# PowerB.net
KiCad netlist of a schematic drawn in Altium Designer
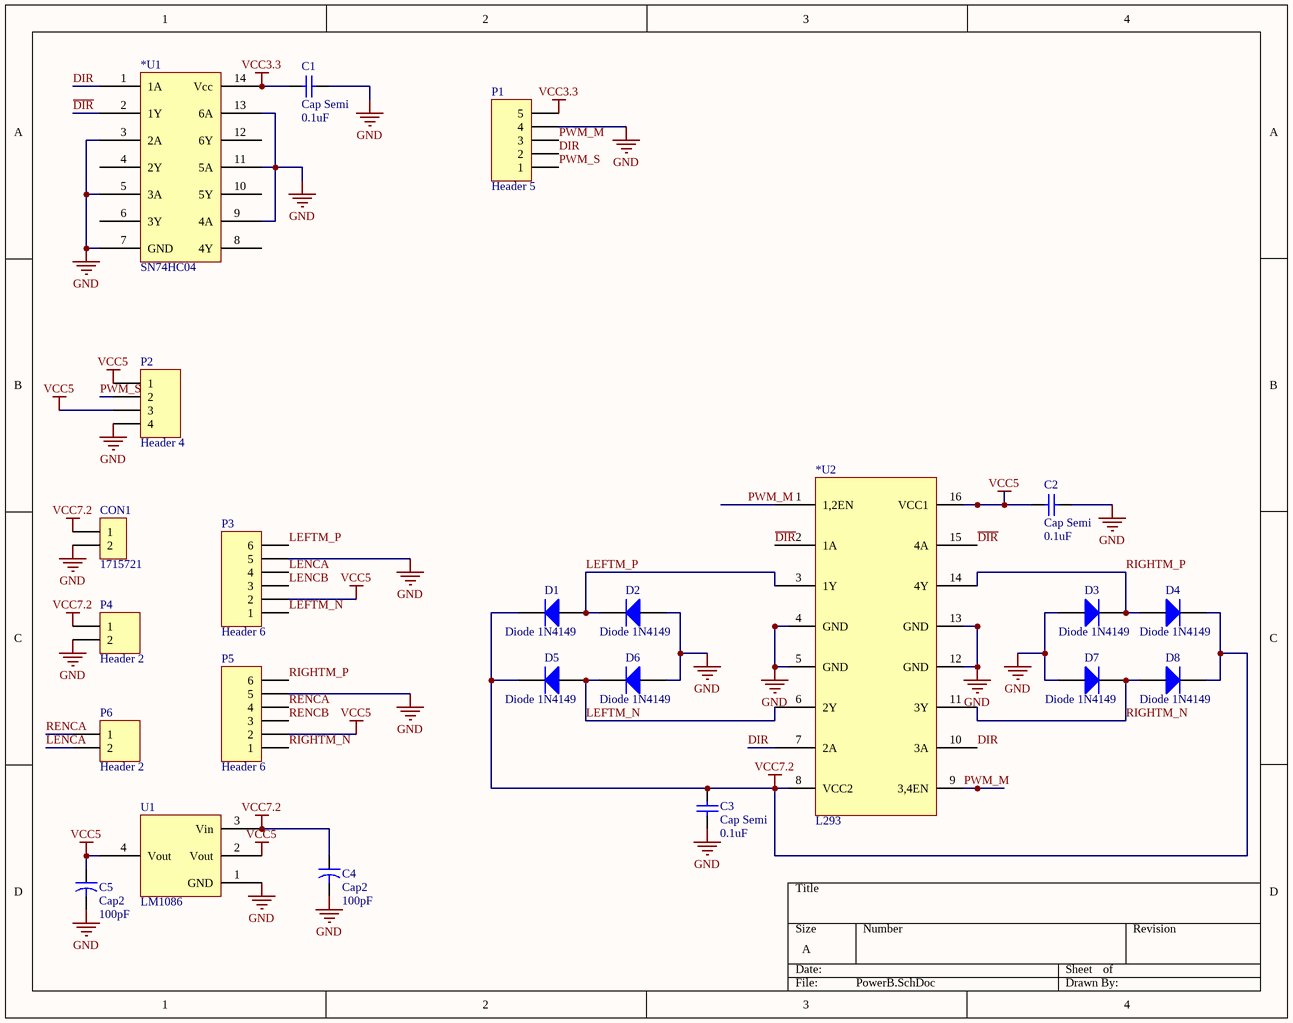
[diagram p0: PowerB.SchDoc]

(export (version "E")
  (design (tool "Eeschema 10.0.6"))
  (components
    (comp (ref "*U1")
      (value "SN74HC04")
      (footprint "Atmel Industrial Control:DIP14")
      (libsource (lib "SN74HC04") (part "SN74HC04"))
    )
    (comp (ref "*U2")
      (value "L293")
      (footprint "Dallas Communication PCM Circuit:DIP16")
      (libsource (lib "L293") (part "L293"))
    )
    (comp (ref "C1")
      (value "Cap Semi")
      (footprint "C1206")
      (description "Capacitor (Semiconductor SIM Model)")
      (fields (field (name "ALTIUM_VALUE") "0.1uF") (field (name "PUBLISHER") "Altium Limited"))
      (libsource (lib "Miscellaneous Devices") (part "Cap Semi"))
    )
    (comp (ref "C2")
      (value "Cap Semi")
      (footprint "C1206")
      (description "Capacitor (Semiconductor SIM Model)")
      (fields (field (name "ALTIUM_VALUE") "0.1uF") (field (name "PUBLISHER") "Altium Limited"))
      (libsource (lib "Miscellaneous Devices") (part "Cap Semi"))
    )
    (comp (ref "C3")
      (value "Cap Semi")
      (footprint "C1206")
      (description "Capacitor (Semiconductor SIM Model)")
      (fields (field (name "ALTIUM_VALUE") "0.1uF") (field (name "PUBLISHER") "Altium Limited"))
      (libsource (lib "Miscellaneous Devices") (part "Cap Semi"))
    )
    (comp (ref "C4")
      (value "Cap2")
      (footprint "100EFK")
      (description "Capacitor")
      (fields (field (name "ALTIUM_VALUE") "100pF") (field (name "PUBLISHER") "Altium Limited"))
      (libsource (lib "Miscellaneous Devices") (part "Cap2"))
    )
    (comp (ref "C5")
      (value "Cap2")
      (footprint "100EFK")
      (description "Capacitor")
      (fields (field (name "ALTIUM_VALUE") "100pF") (field (name "PUBLISHER") "Altium Limited"))
      (libsource (lib "Miscellaneous Devices") (part "Cap2"))
    )
    (comp (ref "CON1")
      (value "1715721")
      (footprint "1715721")
      (description "Conn Term (screw) Block 5mm 2Pos 18mm height")
      (fields (field (name "DIGIKEY PART NUMBER") "277-1022-ND"))
      (libsource (lib "Phoenix ") (part "1715721"))
    )
    (comp (ref "D1")
      (value "Diode 1N4149")
      (footprint "DO-35A")
      (description "1 Amp General Purpose Rectifier")
      (fields (field (name "PUBLISHER") "Altium Limited"))
      (libsource (lib "Miscellaneous Devices") (part "Diode 1N4007"))
    )
    (comp (ref "D2")
      (value "Diode 1N4149")
      (footprint "DO-35A")
      (description "1 Amp General Purpose Rectifier")
      (fields (field (name "PUBLISHER") "Altium Limited"))
      (libsource (lib "Miscellaneous Devices") (part "Diode 1N4007"))
    )
    (comp (ref "D3")
      (value "Diode 1N4149")
      (footprint "DO-35A")
      (description "1 Amp General Purpose Rectifier")
      (fields (field (name "PUBLISHER") "Altium Limited"))
      (libsource (lib "Miscellaneous Devices") (part "Diode 1N4007"))
    )
    (comp (ref "D4")
      (value "Diode 1N4149")
      (footprint "DO-35A")
      (description "1 Amp General Purpose Rectifier")
      (fields (field (name "PUBLISHER") "Altium Limited"))
      (libsource (lib "Miscellaneous Devices") (part "Diode 1N4007"))
    )
    (comp (ref "D5")
      (value "Diode 1N4149")
      (footprint "DO-35A")
      (description "1 Amp General Purpose Rectifier")
      (fields (field (name "PUBLISHER") "Altium Limited"))
      (libsource (lib "Miscellaneous Devices") (part "Diode 1N4007"))
    )
    (comp (ref "D6")
      (value "Diode 1N4149")
      (footprint "DO-35A")
      (description "1 Amp General Purpose Rectifier")
      (fields (field (name "PUBLISHER") "Altium Limited"))
      (libsource (lib "Miscellaneous Devices") (part "Diode 1N4007"))
    )
    (comp (ref "D7")
      (value "Diode 1N4149")
      (footprint "DO-35A")
      (description "1 Amp General Purpose Rectifier")
      (fields (field (name "PUBLISHER") "Altium Limited"))
      (libsource (lib "Miscellaneous Devices") (part "Diode 1N4007"))
    )
    (comp (ref "D8")
      (value "Diode 1N4149")
      (footprint "DO-35A")
      (description "1 Amp General Purpose Rectifier")
      (fields (field (name "PUBLISHER") "Altium Limited"))
      (libsource (lib "Miscellaneous Devices") (part "Diode 1N4007"))
    )
    (comp (ref "P1")
      (value "Header 5")
      (footprint "HDR1X5")
      (description "Header, 5-Pin")
      (fields (field (name "PUBLISHER") "Altium Limited"))
      (libsource (lib "Miscellaneous Connectors") (part "Header 5"))
    )
    (comp (ref "P2")
      (value "Header 4")
      (footprint "HDR1X4")
      (description "Header, 4-Pin")
      (fields (field (name "PUBLISHER") "Altium Limited"))
      (libsource (lib "Miscellaneous Connectors") (part "Header 4"))
    )
    (comp (ref "P3")
      (value "Header 6")
      (footprint "HDR1X6")
      (description "Header, 6-Pin")
      (fields (field (name "PUBLISHER") "Altium Limited"))
      (libsource (lib "Miscellaneous Connectors") (part "Header 6"))
    )
    (comp (ref "P4")
      (value "Header 2")
      (footprint "HDR1X2")
      (description "Header, 2-Pin")
      (fields (field (name "PUBLISHER") "Altium Limited"))
      (libsource (lib "Miscellaneous Connectors") (part "Header 2"))
    )
    (comp (ref "P5")
      (value "Header 6")
      (footprint "HDR1X6")
      (description "Header, 6-Pin")
      (fields (field (name "PUBLISHER") "Altium Limited"))
      (libsource (lib "Miscellaneous Connectors") (part "Header 6"))
    )
    (comp (ref "P6")
      (value "Header 2")
      (footprint "HDR1X2")
      (description "Header, 2-Pin")
      (fields (field (name "PUBLISHER") "Altium Limited"))
      (libsource (lib "Miscellaneous Connectors") (part "Header 2"))
    )
    (comp (ref "U1") (value "LM1086") (footprint "DPAK254") (libsource (lib "LM1086") (part "LM1086")))
  )
  (nets
    (net (code "1") (name "/DIR") (class "Default")
      (node (ref "*U1") (pin "1") (pinfunction "1A_1") (pintype "passive"))
      (node (ref "*U2") (pin "10") (pinfunction "3A_10") (pintype "passive"))
      (node (ref "*U2") (pin "7") (pinfunction "2A_7") (pintype "passive"))
      (node (ref "P1") (pin "2") (pinfunction "2_2") (pintype "passive"))
    )
    (net (code "2") (name "/LEFTM_N") (class "Default")
      (node (ref "*U2") (pin "6") (pinfunction "2Y_6") (pintype "passive"))
      (node (ref "D5") (pin "1") (pinfunction "A_1") (pintype "passive"))
      (node (ref "D6") (pin "2") (pinfunction "K_2") (pintype "passive"))
      (node (ref "P3") (pin "1") (pinfunction "1_1") (pintype "passive"))
    )
    (net (code "3") (name "/LEFTM_P") (class "Default")
      (node (ref "*U2") (pin "3") (pinfunction "1Y_3") (pintype "passive"))
      (node (ref "D1") (pin "1") (pinfunction "A_1") (pintype "passive"))
      (node (ref "D2") (pin "2") (pinfunction "K_2") (pintype "passive"))
      (node (ref "P3") (pin "6") (pinfunction "6_6") (pintype "passive"))
    )
    (net (code "4") (name "/LENCA") (class "Default")
      (node (ref "P3") (pin "4") (pinfunction "4_4") (pintype "passive"))
      (node (ref "P6") (pin "2") (pinfunction "2_2") (pintype "passive"))
    )
    (net (code "5") (name "/LENCB") (class "Default")
      (node (ref "P3") (pin "3") (pinfunction "3_3") (pintype "passive"))
    )
    (net (code "6") (name "/PWM_M") (class "Default")
      (node (ref "*U2") (pin "1") (pinfunction "1,2EN_1") (pintype "passive"))
      (node (ref "*U2") (pin "9") (pinfunction "3,4EN_9") (pintype "passive"))
      (node (ref "P1") (pin "3") (pinfunction "3_3") (pintype "passive"))
    )
    (net (code "7") (name "/PWM_S") (class "Default")
      (node (ref "P1") (pin "1") (pinfunction "1_1") (pintype "passive"))
      (node (ref "P2") (pin "2") (pinfunction "2_2") (pintype "passive"))
    )
    (net (code "8") (name "/RENCA") (class "Default")
      (node (ref "P5") (pin "4") (pinfunction "4_4") (pintype "passive"))
      (node (ref "P6") (pin "1") (pinfunction "1_1") (pintype "passive"))
    )
    (net (code "9") (name "/RENCB") (class "Default")
      (node (ref "P5") (pin "3") (pinfunction "3_3") (pintype "passive"))
    )
    (net (code "10") (name "/RIGHTM_N") (class "Default")
      (node (ref "*U2") (pin "11") (pinfunction "3Y_11") (pintype "passive"))
      (node (ref "D7") (pin "2") (pinfunction "K_2") (pintype "passive"))
      (node (ref "D8") (pin "1") (pinfunction "A_1") (pintype "passive"))
      (node (ref "P5") (pin "1") (pinfunction "1_1") (pintype "passive"))
    )
    (net (code "11") (name "/RIGHTM_P") (class "Default")
      (node (ref "*U2") (pin "14") (pinfunction "4Y_14") (pintype "passive"))
      (node (ref "D3") (pin "2") (pinfunction "K_2") (pintype "passive"))
      (node (ref "D4") (pin "1") (pinfunction "A_1") (pintype "passive"))
      (node (ref "P5") (pin "6") (pinfunction "6_6") (pintype "passive"))
    )
    (net (code "12") (name "/~{DIR}") (class "Default")
      (node (ref "*U1") (pin "2") (pinfunction "1Y_2") (pintype "passive"))
      (node (ref "*U2") (pin "15") (pinfunction "4A_15") (pintype "passive"))
      (node (ref "*U2") (pin "2") (pinfunction "1A_2") (pintype "passive"))
    )
    (net (code "13") (name "GND") (class "Default")
      (node (ref "*U1") (pin "11") (pinfunction "5A_11") (pintype "passive"))
      (node (ref "*U1") (pin "13") (pinfunction "6A_13") (pintype "passive"))
      (node (ref "*U1") (pin "3") (pinfunction "2A_3") (pintype "passive"))
      (node (ref "*U1") (pin "5") (pinfunction "3A_5") (pintype "passive"))
      (node (ref "*U1") (pin "7") (pinfunction "GND_7") (pintype "passive"))
      (node (ref "*U1") (pin "9") (pinfunction "4A_9") (pintype "passive"))
      (node (ref "*U2") (pin "12") (pinfunction "GND_12") (pintype "passive"))
      (node (ref "*U2") (pin "13") (pinfunction "GND_13") (pintype "passive"))
      (node (ref "*U2") (pin "4") (pinfunction "GND_4") (pintype "passive"))
      (node (ref "*U2") (pin "5") (pinfunction "GND_5") (pintype "passive"))
      (node (ref "C1") (pin "2") (pinfunction "2_2") (pintype "passive"))
      (node (ref "C2") (pin "1") (pinfunction "1_1") (pintype "passive"))
      (node (ref "C3") (pin "1") (pinfunction "1_1") (pintype "passive"))
      (node (ref "C4") (pin "2") (pinfunction "2_2") (pintype "passive"))
      (node (ref "C5") (pin "2") (pinfunction "2_2") (pintype "passive"))
      (node (ref "CON1") (pin "2") (pinfunction "2_2") (pintype "passive"))
      (node (ref "D2") (pin "1") (pinfunction "A_1") (pintype "passive"))
      (node (ref "D3") (pin "1") (pinfunction "A_1") (pintype "passive"))
      (node (ref "D6") (pin "1") (pinfunction "A_1") (pintype "passive"))
      (node (ref "D7") (pin "1") (pinfunction "A_1") (pintype "passive"))
      (node (ref "P1") (pin "4") (pinfunction "4_4") (pintype "passive"))
      (node (ref "P2") (pin "4") (pinfunction "4_4") (pintype "passive"))
      (node (ref "P3") (pin "5") (pinfunction "5_5") (pintype "passive"))
      (node (ref "P4") (pin "2") (pinfunction "2_2") (pintype "passive"))
      (node (ref "P5") (pin "5") (pinfunction "5_5") (pintype "passive"))
      (node (ref "U1") (pin "1") (pinfunction "GND_1") (pintype "passive"))
    )
    (net (code "14") (name "VCC3.3") (class "Default")
      (node (ref "*U1") (pin "14") (pinfunction "Vcc_14") (pintype "passive"))
      (node (ref "C1") (pin "1") (pinfunction "1_1") (pintype "passive"))
      (node (ref "P1") (pin "5") (pinfunction "5_5") (pintype "passive"))
    )
    (net (code "15") (name "VCC5") (class "Default")
      (node (ref "*U2") (pin "16") (pinfunction "VCC1_16") (pintype "passive"))
      (node (ref "C2") (pin "2") (pinfunction "2_2") (pintype "passive"))
      (node (ref "C5") (pin "1") (pinfunction "1_1") (pintype "passive"))
      (node (ref "P2") (pin "1") (pinfunction "1_1") (pintype "passive"))
      (node (ref "P2") (pin "3") (pinfunction "3_3") (pintype "passive"))
      (node (ref "P3") (pin "2") (pinfunction "2_2") (pintype "passive"))
      (node (ref "P5") (pin "2") (pinfunction "2_2") (pintype "passive"))
      (node (ref "U1") (pin "2") (pinfunction "Vout_2") (pintype "passive"))
      (node (ref "U1") (pin "4") (pinfunction "Vout_4") (pintype "passive"))
    )
    (net (code "16") (name "VCC7.2") (class "Default")
      (node (ref "*U2") (pin "8") (pinfunction "VCC2_8") (pintype "passive"))
      (node (ref "C3") (pin "2") (pinfunction "2_2") (pintype "passive"))
      (node (ref "C4") (pin "1") (pinfunction "1_1") (pintype "passive"))
      (node (ref "CON1") (pin "1") (pinfunction "1_1") (pintype "passive"))
      (node (ref "D1") (pin "2") (pinfunction "K_2") (pintype "passive"))
      (node (ref "D4") (pin "2") (pinfunction "K_2") (pintype "passive"))
      (node (ref "D5") (pin "2") (pinfunction "K_2") (pintype "passive"))
      (node (ref "D8") (pin "2") (pinfunction "K_2") (pintype "passive"))
      (node (ref "P4") (pin "1") (pinfunction "1_1") (pintype "passive"))
      (node (ref "U1") (pin "3") (pinfunction "Vin_3") (pintype "passive"))
    )
    (net (code "17") (name "unconnected-(*U1-2Y-Pad4)") (class "Default")
      (node (ref "*U1") (pin "4") (pinfunction "2Y_4") (pintype "passive"))
    )
    (net (code "18") (name "unconnected-(*U1-3Y-Pad6)") (class "Default")
      (node (ref "*U1") (pin "6") (pinfunction "3Y_6") (pintype "passive"))
    )
    (net (code "19") (name "unconnected-(*U1-4Y-Pad8)") (class "Default")
      (node (ref "*U1") (pin "8") (pinfunction "4Y_8") (pintype "passive"))
    )
    (net (code "20") (name "unconnected-(*U1-5Y-Pad10)") (class "Default")
      (node (ref "*U1") (pin "10") (pinfunction "5Y_10") (pintype "passive"))
    )
    (net (code "21") (name "unconnected-(*U1-6Y-Pad12)") (class "Default")
      (node (ref "*U1") (pin "12") (pinfunction "6Y_12") (pintype "passive"))
    )
  )
)
